# at86rf_mk2.net
KiCad netlist of a schematic drawn in EAGLE
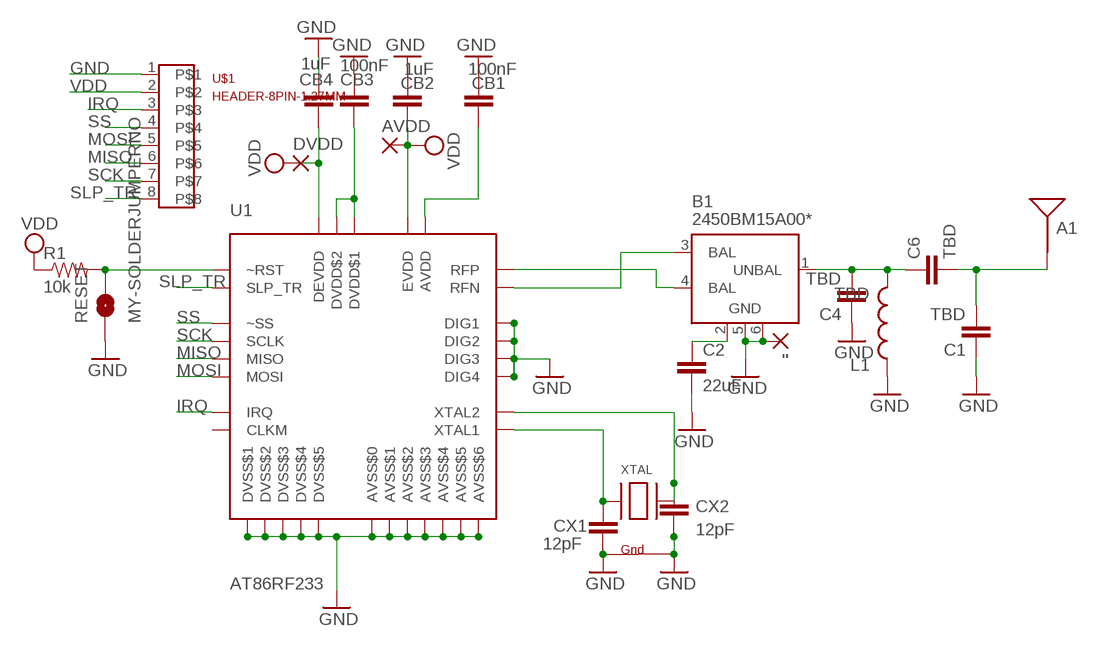
[diagram p0: schematic, sheet 1]

(export (version "E")
  (design (tool "Eeschema 10.0.6"))
  (components
    (comp (ref "'")
      (value "VIAPADNOTHERMAL")
      (footprint "eagle-import:VIAPAD13MIL-NOTHERMAL")
      (libsource (lib "eagle-import") (part "VIAPADNOTHERMAL"))
    )
    (comp (ref "''")
      (value "VIAPADNOTHERMAL")
      (footprint "eagle-import:VIAPAD13MIL-NOTHERMAL")
      (libsource (lib "eagle-import") (part "VIAPADNOTHERMAL"))
    )
    (comp (ref "A1")
      (value "ANTENNA2SMD5")
      (footprint "eagle-import:ANTENNA-CHIP5")
      (libsource (lib "eagle-import") (part "ANTENNA2SMD5"))
    )
    (comp (ref "AVDD")
      (value "VIAPADNOPASTE")
      (footprint "eagle-import:PAD-1-NOPASTE")
      (libsource (lib "eagle-import") (part "VIAPADNOPASTE"))
    )
    (comp (ref "B1")
      (value "2450BM15A00*")
      (footprint "eagle-import:2450BM15A0002")
      (libsource (lib "eagle-import") (part "2450BM15A00"))
    )
    (comp (ref "C1")
      (value "TBD")
      (footprint "eagle-import:0402-CAP")
      (libsource (lib "eagle-import") (part "SparkFun-Passives_CAP0402-CAP"))
    )
    (comp (ref "C2")
      (value "22uF")
      (footprint "eagle-import:0402-CAP")
      (libsource (lib "eagle-import") (part "SparkFun-Passives_CAP0402-CAP"))
    )
    (comp (ref "C4")
      (value "TBD")
      (footprint "eagle-import:0402-CAP")
      (libsource (lib "eagle-import") (part "SparkFun-Passives_CAP0402-CAP"))
    )
    (comp (ref "C6")
      (value "TBD")
      (footprint "eagle-import:0402-CAP")
      (libsource (lib "eagle-import") (part "SparkFun-Passives_CAP0402-CAP"))
    )
    (comp (ref "CB1")
      (value "100nF")
      (footprint "eagle-import:0402-CAP")
      (libsource (lib "eagle-import") (part "CAP0402-CAP"))
    )
    (comp (ref "CB2")
      (value "1uF")
      (footprint "eagle-import:0603-CAP")
      (libsource (lib "eagle-import") (part "CAP0603-CAP"))
    )
    (comp (ref "CB3")
      (value "100nF")
      (footprint "eagle-import:0402-CAP")
      (libsource (lib "eagle-import") (part "CAP0402-CAP"))
    )
    (comp (ref "CB4")
      (value "1uF")
      (footprint "eagle-import:0603-CAP")
      (libsource (lib "eagle-import") (part "CAP0603-CAP"))
    )
    (comp (ref "CX1")
      (value "12pF")
      (footprint "eagle-import:0402-CAP")
      (libsource (lib "eagle-import") (part "CAP0402-CAP"))
    )
    (comp (ref "CX2")
      (value "12pF")
      (footprint "eagle-import:0402-CAP")
      (libsource (lib "eagle-import") (part "CAP0402-CAP"))
    )
    (comp (ref "DVDD")
      (value "VIAPADNOPASTE")
      (footprint "eagle-import:PAD-1-NOPASTE")
      (libsource (lib "eagle-import") (part "VIAPADNOPASTE"))
    )
    (comp (ref "L1")
      (value "TBD")
      (footprint "eagle-import:C0402")
      (libsource (lib "eagle-import") (part "INDUCTOR0402"))
    )
    (comp (ref "R1")
      (value "10k")
      (footprint "eagle-import:0402-RES")
      (libsource (lib "eagle-import") (part "RESISTOR0402-RES"))
    )
    (comp (ref "RESET")
      (value "MY-SOLDERJUMPERNO")
      (footprint "eagle-import:SJ_2S-NO")
      (libsource (lib "eagle-import") (part "MY-SOLDERJUMPERNO"))
    )
    (comp (ref "U$1")
      (value "HEADER-8PIN-1.27MM")
      (footprint "eagle-import:1X08-1.27MM")
      (libsource (lib "eagle-import") (part "HEADER-8PIN-1.27MM"))
    )
    (comp (ref "U1")
      (value "AT86RF233")
      (footprint "eagle-import:QFN-32")
      (libsource (lib "eagle-import") (part "AT86RF212BQFN32"))
    )
    (comp (ref "XTAL")
      (value "XTAL-4-3225")
      (footprint "eagle-import:NX3225")
      (libsource (lib "eagle-import") (part "XTAL-4-3225"))
    )
  )
  (nets
    (net (code "1") (name "/IRQ") (class "Default")
      (node (ref "U$1") (pin "3") (pinfunction "P$3_3") (pintype "bidirectional"))
      (node (ref "U1") (pin "24") (pinfunction "IRQ_24") (pintype "bidirectional"))
    )
    (net (code "2") (name "/MISO") (class "Default")
      (node (ref "U$1") (pin "6") (pinfunction "P$6_6") (pintype "bidirectional"))
      (node (ref "U1") (pin "20") (pinfunction "MISO_20") (pintype "bidirectional"))
    )
    (net (code "3") (name "/MOSI") (class "Default")
      (node (ref "U$1") (pin "5") (pinfunction "P$5_5") (pintype "bidirectional"))
      (node (ref "U1") (pin "22") (pinfunction "MOSI_22") (pintype "bidirectional"))
    )
    (net (code "4") (name "/SCK") (class "Default")
      (node (ref "U$1") (pin "7") (pinfunction "P$7_7") (pintype "bidirectional"))
      (node (ref "U1") (pin "19") (pinfunction "SCLK_19") (pintype "bidirectional"))
    )
    (net (code "5") (name "/SLP_TR") (class "Default")
      (node (ref "U$1") (pin "8") (pinfunction "P$8_8") (pintype "bidirectional"))
      (node (ref "U1") (pin "11") (pinfunction "SLP_TR_11") (pintype "bidirectional"))
    )
    (net (code "6") (name "/SS") (class "Default")
      (node (ref "U$1") (pin "4") (pinfunction "P$4_4") (pintype "bidirectional"))
      (node (ref "U1") (pin "23") (pinfunction "~{SS}_23") (pintype "bidirectional"))
    )
    (net (code "7") (name "GND") (class "Default")
      (node (ref "'") (pin "1") (pinfunction "P_1") (pintype "passive"))
      (node (ref "''") (pin "1") (pinfunction "P_1") (pintype "passive"))
      (node (ref "B1") (pin "5") (pinfunction "GND_5") (pintype "passive"))
      (node (ref "B1") (pin "6") (pinfunction "GND_6") (pintype "passive"))
      (node (ref "C1") (pin "1") (pinfunction "1_1") (pintype "passive"))
      (node (ref "C2") (pin "2") (pinfunction "2_2") (pintype "passive"))
      (node (ref "C4") (pin "1") (pinfunction "1_1") (pintype "passive"))
      (node (ref "CB1") (pin "1") (pinfunction "1_1") (pintype "passive"))
      (node (ref "CB2") (pin "1") (pinfunction "1_1") (pintype "passive"))
      (node (ref "CB3") (pin "1") (pinfunction "1_1") (pintype "passive"))
      (node (ref "CB4") (pin "1") (pinfunction "1_1") (pintype "passive"))
      (node (ref "CX1") (pin "2") (pinfunction "2_2") (pintype "passive"))
      (node (ref "CX2") (pin "2") (pinfunction "2_2") (pintype "passive"))
      (node (ref "L1") (pin "1") (pinfunction "1_1") (pintype "passive"))
      (node (ref "RESET") (pin "1") (pinfunction "1_1") (pintype "passive"))
      (node (ref "U$1") (pin "1") (pinfunction "P$1_1") (pintype "bidirectional"))
      (node (ref "U1") (pin "1") (pinfunction "DIG3_1") (pintype "bidirectional"))
      (node (ref "U1") (pin "10") (pinfunction "DIG2_10") (pintype "bidirectional"))
      (node (ref "U1") (pin "12") (pinfunction "DVSS$2_12") (pintype "bidirectional"))
      (node (ref "U1") (pin "16") (pinfunction "DVSS$3_16") (pintype "bidirectional"))
      (node (ref "U1") (pin "18") (pinfunction "DVSS$4_18") (pintype "bidirectional"))
      (node (ref "U1") (pin "2") (pinfunction "DIG4_2") (pintype "bidirectional"))
      (node (ref "U1") (pin "21") (pinfunction "DVSS$5_21") (pintype "bidirectional"))
      (node (ref "U1") (pin "27") (pinfunction "AVSS$3_27") (pintype "bidirectional"))
      (node (ref "U1") (pin "3") (pinfunction "AVSS$1_3") (pintype "bidirectional"))
      (node (ref "U1") (pin "30") (pinfunction "AVSS$4_30") (pintype "bidirectional"))
      (node (ref "U1") (pin "31") (pinfunction "AVSS$5_31") (pintype "bidirectional"))
      (node (ref "U1") (pin "32") (pinfunction "AVSS$6_32") (pintype "bidirectional"))
      (node (ref "U1") (pin "6") (pinfunction "AVSS$2_6") (pintype "bidirectional"))
      (node (ref "U1") (pin "7") (pinfunction "DVSS$1_7") (pintype "bidirectional"))
      (node (ref "U1") (pin "9") (pinfunction "DIG1_9") (pintype "bidirectional"))
      (node (ref "U1") (pin "EP") (pinfunction "AVSS$0_EP") (pintype "bidirectional"))
      (node (ref "XTAL") (pin "2") (pinfunction "G2_2") (pintype "power_in"))
      (node (ref "XTAL") (pin "4") (pinfunction "G1_4") (pintype "power_in"))
    )
    (net (code "8") (name "Net-(A1-SIGNAL)") (class "Default")
      (node (ref "A1") (pin "FEED") (pinfunction "SIGNAL_FEED") (pintype "bidirectional"))
      (node (ref "C1") (pin "2") (pinfunction "2_2") (pintype "passive"))
      (node (ref "C6") (pin "2") (pinfunction "2_2") (pintype "passive"))
    )
    (net (code "9") (name "Net-(B1-GND-Pad2)") (class "Default")
      (node (ref "B1") (pin "2") (pinfunction "GND_2") (pintype "passive"))
      (node (ref "C2") (pin "1") (pinfunction "1_1") (pintype "passive"))
    )
    (net (code "10") (name "Net-(B1-UNBAL)") (class "Default")
      (node (ref "B1") (pin "1") (pinfunction "UNBAL_1") (pintype "passive"))
      (node (ref "C4") (pin "2") (pinfunction "2_2") (pintype "passive"))
      (node (ref "C6") (pin "1") (pinfunction "1_1") (pintype "passive"))
      (node (ref "L1") (pin "2") (pinfunction "2_2") (pintype "passive"))
    )
    (net (code "11") (name "Net-(U1-AVDD)") (class "Default")
      (node (ref "CB1") (pin "2") (pinfunction "2_2") (pintype "passive"))
      (node (ref "U1") (pin "29") (pinfunction "AVDD_29") (pintype "bidirectional"))
    )
    (net (code "12") (name "Net-(U1-DVDD$1)") (class "Default")
      (node (ref "CB3") (pin "2") (pinfunction "2_2") (pintype "passive"))
      (node (ref "U1") (pin "13") (pinfunction "DVDD$1_13") (pintype "bidirectional"))
      (node (ref "U1") (pin "14") (pinfunction "DVDD$2_14") (pintype "bidirectional"))
    )
    (net (code "13") (name "Net-(U1-RFN)") (class "Default")
      (node (ref "B1") (pin "3") (pinfunction "BAL_3") (pintype "passive"))
      (node (ref "U1") (pin "5") (pinfunction "RFN_5") (pintype "bidirectional"))
    )
    (net (code "14") (name "Net-(U1-RFP)") (class "Default")
      (node (ref "B1") (pin "4") (pinfunction "BAL_4") (pintype "passive"))
      (node (ref "U1") (pin "4") (pinfunction "RFP_4") (pintype "bidirectional"))
    )
    (net (code "15") (name "Net-(U1-XTAL1)") (class "Default")
      (node (ref "CX1") (pin "1") (pinfunction "1_1") (pintype "passive"))
      (node (ref "U1") (pin "26") (pinfunction "XTAL1_26") (pintype "bidirectional"))
      (node (ref "XTAL") (pin "1") (pinfunction "X1_1") (pintype "bidirectional"))
    )
    (net (code "16") (name "Net-(U1-XTAL2)") (class "Default")
      (node (ref "CX2") (pin "1") (pinfunction "1_1") (pintype "passive"))
      (node (ref "U1") (pin "25") (pinfunction "XTAL2_25") (pintype "bidirectional"))
      (node (ref "XTAL") (pin "3") (pinfunction "X2_3") (pintype "bidirectional"))
    )
    (net (code "17") (name "Net-(U1-~{RST})") (class "Default")
      (node (ref "R1") (pin "2") (pinfunction "2_2") (pintype "passive"))
      (node (ref "RESET") (pin "2") (pinfunction "2_2") (pintype "passive"))
      (node (ref "U1") (pin "8") (pinfunction "~{RST}_8") (pintype "bidirectional"))
    )
    (net (code "18") (name "VDD") (class "Default")
      (node (ref "AVDD") (pin "P$1") (pinfunction "P_P$1") (pintype "passive"))
      (node (ref "CB2") (pin "2") (pinfunction "2_2") (pintype "passive"))
      (node (ref "CB4") (pin "2") (pinfunction "2_2") (pintype "passive"))
      (node (ref "DVDD") (pin "P$1") (pinfunction "P_P$1") (pintype "passive"))
      (node (ref "R1") (pin "1") (pinfunction "1_1") (pintype "passive"))
      (node (ref "U$1") (pin "2") (pinfunction "P$2_2") (pintype "bidirectional"))
      (node (ref "U1") (pin "15") (pinfunction "DEVDD_15") (pintype "bidirectional"))
      (node (ref "U1") (pin "28") (pinfunction "EVDD_28") (pintype "bidirectional"))
    )
    (net (code "19") (name "unconnected-(U1-CLKM-Pad17)") (class "Default")
      (node (ref "U1") (pin "17") (pinfunction "CLKM_17") (pintype "bidirectional"))
    )
  )
)
